# W681A.net
KiCad netlist of a schematic drawn in EAGLE
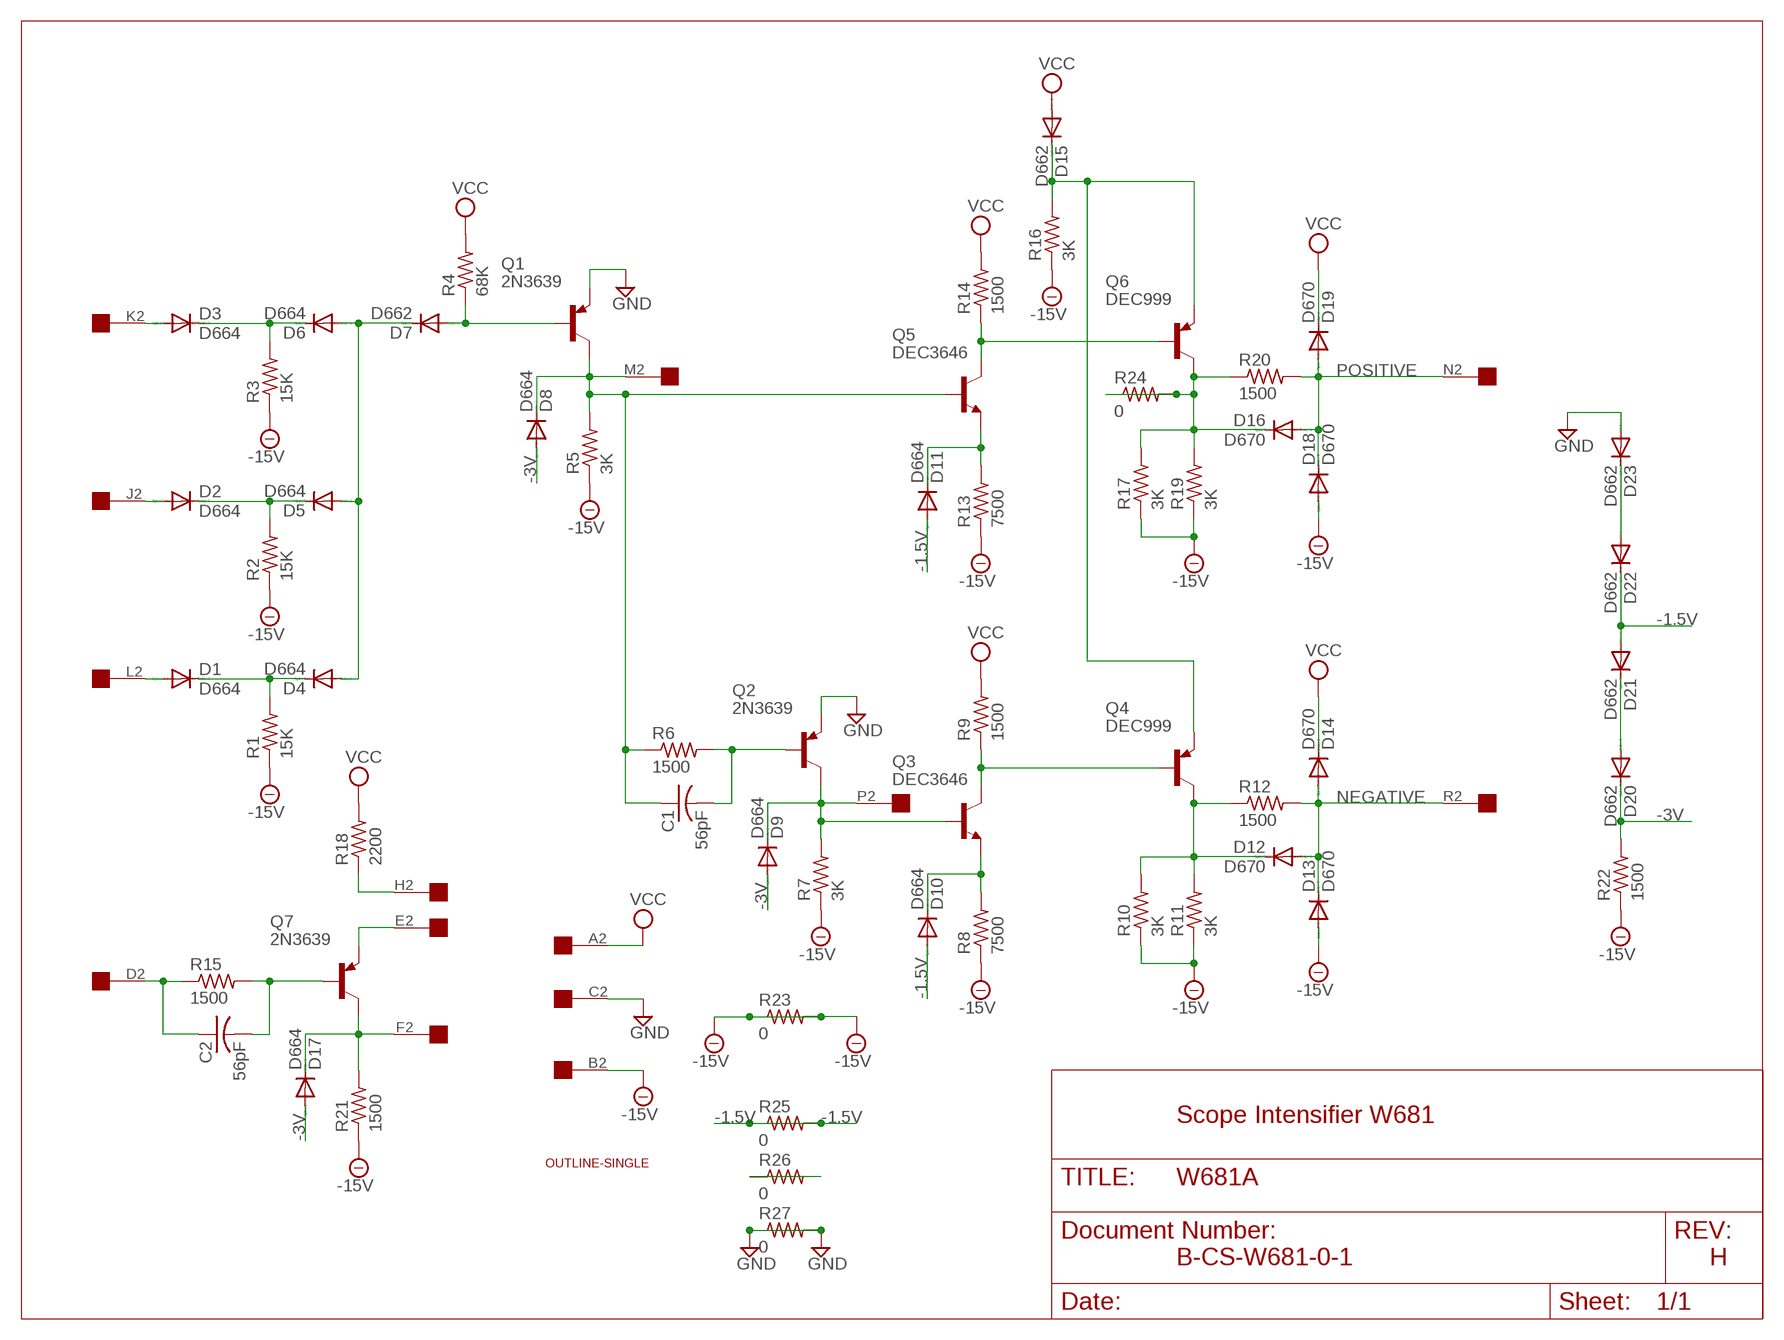
[diagram p0: schematic, sheet 1]

(export (version "E")
  (design (tool "Eeschema 10.0.6"))
  (components
    (comp (ref "C1")
      (value "56pF")
      (footprint "eagle-import:C063-025X075")
      (libsource (lib "eagle-import") (part "C-US"))
    )
    (comp (ref "C2")
      (value "56pF")
      (footprint "eagle-import:C063-025X075")
      (libsource (lib "eagle-import") (part "C-US"))
    )
    (comp (ref "D1")
      (value "D664")
      (footprint "eagle-import:DO35-10")
      (libsource (lib "eagle-import") (part "DIODE-DO35-10"))
    )
    (comp (ref "D2")
      (value "D664")
      (footprint "eagle-import:DO35-10")
      (libsource (lib "eagle-import") (part "DIODE-DO35-10"))
    )
    (comp (ref "D3")
      (value "D664")
      (footprint "eagle-import:DO35-10")
      (libsource (lib "eagle-import") (part "DIODE-DO35-10"))
    )
    (comp (ref "D4")
      (value "D664")
      (footprint "eagle-import:DO35-10")
      (libsource (lib "eagle-import") (part "DIODE-DO35-10"))
    )
    (comp (ref "D5")
      (value "D664")
      (footprint "eagle-import:DO35-10")
      (libsource (lib "eagle-import") (part "DIODE-DO35-10"))
    )
    (comp (ref "D6")
      (value "D664")
      (footprint "eagle-import:DO35-10")
      (libsource (lib "eagle-import") (part "DIODE-DO35-10"))
    )
    (comp (ref "D7")
      (value "D662")
      (footprint "eagle-import:DO35-10")
      (libsource (lib "eagle-import") (part "DIODE-DO35-10"))
    )
    (comp (ref "D8")
      (value "D664")
      (footprint "eagle-import:DO35-10")
      (libsource (lib "eagle-import") (part "DIODE-DO35-10"))
    )
    (comp (ref "D9")
      (value "D664")
      (footprint "eagle-import:DO35-10")
      (libsource (lib "eagle-import") (part "DIODE-DO35-10"))
    )
    (comp (ref "D10")
      (value "D664")
      (footprint "eagle-import:DO35-10")
      (libsource (lib "eagle-import") (part "DIODE-DO35-10"))
    )
    (comp (ref "D11")
      (value "D664")
      (footprint "eagle-import:DO35-10")
      (libsource (lib "eagle-import") (part "DIODE-DO35-10"))
    )
    (comp (ref "D12")
      (value "D670")
      (footprint "eagle-import:DO35-10")
      (libsource (lib "eagle-import") (part "DIODE-DO35-10"))
    )
    (comp (ref "D13")
      (value "D670")
      (footprint "eagle-import:DO35-10")
      (libsource (lib "eagle-import") (part "DIODE-DO35-10"))
    )
    (comp (ref "D14")
      (value "D670")
      (footprint "eagle-import:DO35-10")
      (libsource (lib "eagle-import") (part "DIODE-DO35-10"))
    )
    (comp (ref "D15")
      (value "D662")
      (footprint "eagle-import:DO35-10")
      (libsource (lib "eagle-import") (part "DIODE-DO35-10"))
    )
    (comp (ref "D16")
      (value "D670")
      (footprint "eagle-import:DO35-10")
      (libsource (lib "eagle-import") (part "DIODE-DO35-10"))
    )
    (comp (ref "D17")
      (value "D664")
      (footprint "eagle-import:DO35-10")
      (libsource (lib "eagle-import") (part "DIODE-DO35-10"))
    )
    (comp (ref "D18")
      (value "D670")
      (footprint "eagle-import:DO35-10")
      (libsource (lib "eagle-import") (part "DIODE-DO35-10"))
    )
    (comp (ref "D19")
      (value "D670")
      (footprint "eagle-import:DO35-10")
      (libsource (lib "eagle-import") (part "DIODE-DO35-10"))
    )
    (comp (ref "D20")
      (value "D662")
      (footprint "eagle-import:DO35-10")
      (libsource (lib "eagle-import") (part "DIODE-DO35-10"))
    )
    (comp (ref "D21")
      (value "D662")
      (footprint "eagle-import:DO35-10")
      (libsource (lib "eagle-import") (part "DIODE-DO35-10"))
    )
    (comp (ref "D22")
      (value "D662")
      (footprint "eagle-import:DO35-10")
      (libsource (lib "eagle-import") (part "DIODE-DO35-10"))
    )
    (comp (ref "D23")
      (value "D662")
      (footprint "eagle-import:DO35-10")
      (libsource (lib "eagle-import") (part "DIODE-DO35-10"))
    )
    (comp (ref "Q1")
      (value "2N3639")
      (footprint "eagle-import:TO5")
      (libsource (lib "eagle-import") (part "-PNP-TO5"))
    )
    (comp (ref "Q2")
      (value "2N3639")
      (footprint "eagle-import:TO5")
      (libsource (lib "eagle-import") (part "-PNP-TO5"))
    )
    (comp (ref "Q3")
      (value "DEC3646")
      (footprint "eagle-import:TO5")
      (libsource (lib "eagle-import") (part "-NPN-TO5"))
    )
    (comp (ref "Q4")
      (value "DEC999")
      (footprint "eagle-import:TO5")
      (libsource (lib "eagle-import") (part "-PNP-TO5"))
    )
    (comp (ref "Q5")
      (value "DEC3646")
      (footprint "eagle-import:TO5")
      (libsource (lib "eagle-import") (part "-NPN-TO5"))
    )
    (comp (ref "Q6")
      (value "DEC999")
      (footprint "eagle-import:TO5")
      (libsource (lib "eagle-import") (part "-PNP-TO5"))
    )
    (comp (ref "Q7")
      (value "2N3639")
      (footprint "eagle-import:TO5")
      (libsource (lib "eagle-import") (part "-PNP-TO5"))
    )
    (comp (ref "R1")
      (value "15K")
      (footprint "eagle-import:0207_10")
      (libsource (lib "eagle-import") (part "R-US_0207/10"))
    )
    (comp (ref "R2")
      (value "15K")
      (footprint "eagle-import:0207_10")
      (libsource (lib "eagle-import") (part "R-US_0207/10"))
    )
    (comp (ref "R3")
      (value "15K")
      (footprint "eagle-import:0207_10")
      (libsource (lib "eagle-import") (part "R-US_0207/10"))
    )
    (comp (ref "R4")
      (value "68K")
      (footprint "eagle-import:0207_10")
      (libsource (lib "eagle-import") (part "R-US_0207/10"))
    )
    (comp (ref "R5")
      (value "3K")
      (footprint "eagle-import:0207_10")
      (libsource (lib "eagle-import") (part "R-US_0207/10"))
    )
    (comp (ref "R6")
      (value "1500")
      (footprint "eagle-import:0207_10")
      (libsource (lib "eagle-import") (part "R-US_0207/10"))
    )
    (comp (ref "R7")
      (value "3K")
      (footprint "eagle-import:0207_10")
      (libsource (lib "eagle-import") (part "R-US_0207/10"))
    )
    (comp (ref "R8")
      (value "7500")
      (footprint "eagle-import:0207_10")
      (libsource (lib "eagle-import") (part "R-US_0207/10"))
    )
    (comp (ref "R9")
      (value "1500")
      (footprint "eagle-import:0207_10")
      (libsource (lib "eagle-import") (part "R-US_0207/10"))
    )
    (comp (ref "R10")
      (value "3K")
      (footprint "eagle-import:0207_10")
      (libsource (lib "eagle-import") (part "R-US_0207/10"))
    )
    (comp (ref "R11")
      (value "3K")
      (footprint "eagle-import:0207_10")
      (libsource (lib "eagle-import") (part "R-US_0207/10"))
    )
    (comp (ref "R12")
      (value "1500")
      (footprint "eagle-import:0207_10")
      (libsource (lib "eagle-import") (part "R-US_0207/10"))
    )
    (comp (ref "R13")
      (value "7500")
      (footprint "eagle-import:0207_10")
      (libsource (lib "eagle-import") (part "R-US_0207/10"))
    )
    (comp (ref "R14")
      (value "1500")
      (footprint "eagle-import:0207_10")
      (libsource (lib "eagle-import") (part "R-US_0207/10"))
    )
    (comp (ref "R15")
      (value "1500")
      (footprint "eagle-import:0207_10")
      (libsource (lib "eagle-import") (part "R-US_0207/10"))
    )
    (comp (ref "R16")
      (value "3K")
      (footprint "eagle-import:0207_10")
      (libsource (lib "eagle-import") (part "R-US_0207/10"))
    )
    (comp (ref "R17")
      (value "3K")
      (footprint "eagle-import:0207_10")
      (libsource (lib "eagle-import") (part "R-US_0207/10"))
    )
    (comp (ref "R18")
      (value "2200")
      (footprint "eagle-import:0207_10")
      (libsource (lib "eagle-import") (part "R-US_0207/10"))
    )
    (comp (ref "R19")
      (value "3K")
      (footprint "eagle-import:0207_10")
      (libsource (lib "eagle-import") (part "R-US_0207/10"))
    )
    (comp (ref "R20")
      (value "1500")
      (footprint "eagle-import:0207_10")
      (libsource (lib "eagle-import") (part "R-US_0207/10"))
    )
    (comp (ref "R21")
      (value "1500")
      (footprint "eagle-import:0207_10")
      (libsource (lib "eagle-import") (part "R-US_0207/10"))
    )
    (comp (ref "R22")
      (value "1500")
      (footprint "eagle-import:0207_10")
      (libsource (lib "eagle-import") (part "R-US_0207/10"))
    )
    (comp (ref "R23")
      (value "0")
      (footprint "eagle-import:0207_10")
      (libsource (lib "eagle-import") (part "R-US_0207/10"))
    )
    (comp (ref "R24")
      (value "0")
      (footprint "eagle-import:0207_10")
      (libsource (lib "eagle-import") (part "R-US_0207/10"))
    )
    (comp (ref "R25")
      (value "0")
      (footprint "eagle-import:0207_10")
      (libsource (lib "eagle-import") (part "R-US_0207/10"))
    )
    (comp (ref "R26")
      (value "0")
      (footprint "eagle-import:0207_10")
      (libsource (lib "eagle-import") (part "R-US_0207/10"))
    )
    (comp (ref "R27")
      (value "0")
      (footprint "eagle-import:0207_10")
      (libsource (lib "eagle-import") (part "R-US_0207/10"))
    )
    (comp (ref "U$1")
      (value "OUTLINE-SINGLE")
      (footprint "eagle-import:SINGLE")
      (libsource (lib "eagle-import") (part "OUTLINE-SINGLE"))
    )
    (comp (ref "U$2")
      (value "EDGE-1")
      (footprint "eagle-import:EDGE-CON1")
      (libsource (lib "eagle-import") (part "EDGE-1"))
    )
  )
  (nets
    (net (code "1") (name "-15V") (class "Default")
      (node (ref "D13") (pin "A") (pinfunction "A_A") (pintype "passive"))
      (node (ref "D18") (pin "A") (pinfunction "A_A") (pintype "passive"))
      (node (ref "R1") (pin "1") (pinfunction "1_1") (pintype "passive"))
      (node (ref "R10") (pin "1") (pinfunction "1_1") (pintype "passive"))
      (node (ref "R11") (pin "1") (pinfunction "1_1") (pintype "passive"))
      (node (ref "R13") (pin "1") (pinfunction "1_1") (pintype "passive"))
      (node (ref "R16") (pin "1") (pinfunction "1_1") (pintype "passive"))
      (node (ref "R17") (pin "1") (pinfunction "1_1") (pintype "passive"))
      (node (ref "R19") (pin "1") (pinfunction "1_1") (pintype "passive"))
      (node (ref "R2") (pin "1") (pinfunction "1_1") (pintype "passive"))
      (node (ref "R21") (pin "1") (pinfunction "1_1") (pintype "passive"))
      (node (ref "R22") (pin "1") (pinfunction "1_1") (pintype "passive"))
      (node (ref "R23") (pin "1") (pinfunction "1_1") (pintype "passive"))
      (node (ref "R23") (pin "2") (pinfunction "2_2") (pintype "passive"))
      (node (ref "R3") (pin "1") (pinfunction "1_1") (pintype "passive"))
      (node (ref "R5") (pin "1") (pinfunction "1_1") (pintype "passive"))
      (node (ref "R7") (pin "1") (pinfunction "1_1") (pintype "passive"))
      (node (ref "R8") (pin "1") (pinfunction "1_1") (pintype "passive"))
      (node (ref "U$2") (pin "B2") (pinfunction "1_B2") (pintype "bidirectional"))
    )
    (net (code "2") (name "/-1.5V") (class "Default")
      (node (ref "D10") (pin "A") (pinfunction "A_A") (pintype "passive"))
      (node (ref "D11") (pin "A") (pinfunction "A_A") (pintype "passive"))
      (node (ref "D21") (pin "A") (pinfunction "A_A") (pintype "passive"))
      (node (ref "D22") (pin "C") (pinfunction "C_C") (pintype "passive"))
      (node (ref "R25") (pin "1") (pinfunction "1_1") (pintype "passive"))
      (node (ref "R25") (pin "2") (pinfunction "2_2") (pintype "passive"))
    )
    (net (code "3") (name "/-3V") (class "Default")
      (node (ref "D17") (pin "A") (pinfunction "A_A") (pintype "passive"))
      (node (ref "D20") (pin "C") (pinfunction "C_C") (pintype "passive"))
      (node (ref "D8") (pin "A") (pinfunction "A_A") (pintype "passive"))
      (node (ref "D9") (pin "A") (pinfunction "A_A") (pintype "passive"))
      (node (ref "R22") (pin "2") (pinfunction "2_2") (pintype "passive"))
    )
    (net (code "4") (name "/NEGATIVE") (class "Default")
      (node (ref "D12") (pin "A") (pinfunction "A_A") (pintype "passive"))
      (node (ref "D13") (pin "C") (pinfunction "C_C") (pintype "passive"))
      (node (ref "D14") (pin "A") (pinfunction "A_A") (pintype "passive"))
      (node (ref "R12") (pin "2") (pinfunction "2_2") (pintype "passive"))
      (node (ref "U$2") (pin "R2") (pinfunction "1_R2") (pintype "bidirectional"))
    )
    (net (code "5") (name "/POSITIVE") (class "Default")
      (node (ref "D16") (pin "A") (pinfunction "A_A") (pintype "passive"))
      (node (ref "D18") (pin "C") (pinfunction "C_C") (pintype "passive"))
      (node (ref "D19") (pin "A") (pinfunction "A_A") (pintype "passive"))
      (node (ref "R20") (pin "2") (pinfunction "2_2") (pintype "passive"))
      (node (ref "U$2") (pin "N2") (pinfunction "1_N2") (pintype "bidirectional"))
    )
    (net (code "6") (name "GND") (class "Default")
      (node (ref "D23") (pin "A") (pinfunction "A_A") (pintype "passive"))
      (node (ref "Q1") (pin "1") (pinfunction "E_1") (pintype "passive"))
      (node (ref "Q2") (pin "1") (pinfunction "E_1") (pintype "passive"))
      (node (ref "R27") (pin "1") (pinfunction "1_1") (pintype "passive"))
      (node (ref "R27") (pin "2") (pinfunction "2_2") (pintype "passive"))
      (node (ref "U$2") (pin "C2") (pinfunction "1_C2") (pintype "bidirectional"))
    )
    (net (code "7") (name "Net-(D1-PadC)") (class "Default")
      (node (ref "D1") (pin "C") (pinfunction "C_C") (pintype "passive"))
      (node (ref "D4") (pin "C") (pinfunction "C_C") (pintype "passive"))
      (node (ref "R1") (pin "2") (pinfunction "2_2") (pintype "passive"))
    )
    (net (code "8") (name "Net-(D2-PadC)") (class "Default")
      (node (ref "D2") (pin "C") (pinfunction "C_C") (pintype "passive"))
      (node (ref "D5") (pin "C") (pinfunction "C_C") (pintype "passive"))
      (node (ref "R2") (pin "2") (pinfunction "2_2") (pintype "passive"))
    )
    (net (code "9") (name "Net-(D3-PadC)") (class "Default")
      (node (ref "D3") (pin "C") (pinfunction "C_C") (pintype "passive"))
      (node (ref "D6") (pin "C") (pinfunction "C_C") (pintype "passive"))
      (node (ref "R3") (pin "2") (pinfunction "2_2") (pintype "passive"))
    )
    (net (code "10") (name "Net-(D4-PadA)") (class "Default")
      (node (ref "D4") (pin "A") (pinfunction "A_A") (pintype "passive"))
      (node (ref "D5") (pin "A") (pinfunction "A_A") (pintype "passive"))
      (node (ref "D6") (pin "A") (pinfunction "A_A") (pintype "passive"))
      (node (ref "D7") (pin "C") (pinfunction "C_C") (pintype "passive"))
    )
    (net (code "11") (name "Net-(D20-PadA)") (class "Default")
      (node (ref "D20") (pin "A") (pinfunction "A_A") (pintype "passive"))
      (node (ref "D21") (pin "C") (pinfunction "C_C") (pintype "passive"))
    )
    (net (code "12") (name "Net-(D22-PadA)") (class "Default")
      (node (ref "D22") (pin "A") (pinfunction "A_A") (pintype "passive"))
      (node (ref "D23") (pin "C") (pinfunction "C_C") (pintype "passive"))
    )
    (net (code "13") (name "Net-(Q1-B)") (class "Default")
      (node (ref "D7") (pin "A") (pinfunction "A_A") (pintype "passive"))
      (node (ref "Q1") (pin "2") (pinfunction "B_2") (pintype "passive"))
      (node (ref "R4") (pin "1") (pinfunction "1_1") (pintype "passive"))
    )
    (net (code "14") (name "Net-(Q1-C)") (class "Default")
      (node (ref "C1") (pin "1") (pinfunction "1_1") (pintype "passive"))
      (node (ref "D8") (pin "C") (pinfunction "C_C") (pintype "passive"))
      (node (ref "Q1") (pin "3") (pinfunction "C_3") (pintype "passive"))
      (node (ref "Q5") (pin "2") (pinfunction "B_2") (pintype "passive"))
      (node (ref "R5") (pin "2") (pinfunction "2_2") (pintype "passive"))
      (node (ref "R6") (pin "1") (pinfunction "1_1") (pintype "passive"))
      (node (ref "U$2") (pin "M2") (pinfunction "1_M2") (pintype "bidirectional"))
    )
    (net (code "15") (name "Net-(Q2-B)") (class "Default")
      (node (ref "C1") (pin "2") (pinfunction "2_2") (pintype "passive"))
      (node (ref "Q2") (pin "2") (pinfunction "B_2") (pintype "passive"))
      (node (ref "R6") (pin "2") (pinfunction "2_2") (pintype "passive"))
    )
    (net (code "16") (name "Net-(Q2-C)") (class "Default")
      (node (ref "D9") (pin "C") (pinfunction "C_C") (pintype "passive"))
      (node (ref "Q2") (pin "3") (pinfunction "C_3") (pintype "passive"))
      (node (ref "Q3") (pin "2") (pinfunction "B_2") (pintype "passive"))
      (node (ref "R7") (pin "2") (pinfunction "2_2") (pintype "passive"))
      (node (ref "U$2") (pin "P2") (pinfunction "1_P2") (pintype "bidirectional"))
    )
    (net (code "17") (name "Net-(Q3-C)") (class "Default")
      (node (ref "Q3") (pin "3") (pinfunction "C_3") (pintype "passive"))
      (node (ref "Q4") (pin "2") (pinfunction "B_2") (pintype "passive"))
      (node (ref "R9") (pin "1") (pinfunction "1_1") (pintype "passive"))
    )
    (net (code "18") (name "Net-(Q3-E)") (class "Default")
      (node (ref "D10") (pin "C") (pinfunction "C_C") (pintype "passive"))
      (node (ref "Q3") (pin "1") (pinfunction "E_1") (pintype "passive"))
      (node (ref "R8") (pin "2") (pinfunction "2_2") (pintype "passive"))
    )
    (net (code "19") (name "Net-(Q4-C)") (class "Default")
      (node (ref "D12") (pin "C") (pinfunction "C_C") (pintype "passive"))
      (node (ref "Q4") (pin "3") (pinfunction "C_3") (pintype "passive"))
      (node (ref "R10") (pin "2") (pinfunction "2_2") (pintype "passive"))
      (node (ref "R11") (pin "2") (pinfunction "2_2") (pintype "passive"))
      (node (ref "R12") (pin "1") (pinfunction "1_1") (pintype "passive"))
    )
    (net (code "20") (name "Net-(Q4-E)") (class "Default")
      (node (ref "D15") (pin "C") (pinfunction "C_C") (pintype "passive"))
      (node (ref "Q4") (pin "1") (pinfunction "E_1") (pintype "passive"))
      (node (ref "Q6") (pin "1") (pinfunction "E_1") (pintype "passive"))
      (node (ref "R16") (pin "2") (pinfunction "2_2") (pintype "passive"))
    )
    (net (code "21") (name "Net-(Q5-C)") (class "Default")
      (node (ref "Q5") (pin "3") (pinfunction "C_3") (pintype "passive"))
      (node (ref "Q6") (pin "2") (pinfunction "B_2") (pintype "passive"))
      (node (ref "R14") (pin "1") (pinfunction "1_1") (pintype "passive"))
    )
    (net (code "22") (name "Net-(Q5-E)") (class "Default")
      (node (ref "D11") (pin "C") (pinfunction "C_C") (pintype "passive"))
      (node (ref "Q5") (pin "1") (pinfunction "E_1") (pintype "passive"))
      (node (ref "R13") (pin "2") (pinfunction "2_2") (pintype "passive"))
    )
    (net (code "23") (name "Net-(Q6-C)") (class "Default")
      (node (ref "D16") (pin "C") (pinfunction "C_C") (pintype "passive"))
      (node (ref "Q6") (pin "3") (pinfunction "C_3") (pintype "passive"))
      (node (ref "R17") (pin "2") (pinfunction "2_2") (pintype "passive"))
      (node (ref "R19") (pin "2") (pinfunction "2_2") (pintype "passive"))
      (node (ref "R20") (pin "1") (pinfunction "1_1") (pintype "passive"))
      (node (ref "R24") (pin "1") (pinfunction "1_1") (pintype "passive"))
      (node (ref "R24") (pin "2") (pinfunction "2_2") (pintype "passive"))
    )
    (net (code "24") (name "Net-(Q7-B)") (class "Default")
      (node (ref "C2") (pin "2") (pinfunction "2_2") (pintype "passive"))
      (node (ref "Q7") (pin "2") (pinfunction "B_2") (pintype "passive"))
      (node (ref "R15") (pin "2") (pinfunction "2_2") (pintype "passive"))
    )
    (net (code "25") (name "Net-(Q7-C)") (class "Default")
      (node (ref "D17") (pin "C") (pinfunction "C_C") (pintype "passive"))
      (node (ref "Q7") (pin "3") (pinfunction "C_3") (pintype "passive"))
      (node (ref "R21") (pin "2") (pinfunction "2_2") (pintype "passive"))
      (node (ref "U$2") (pin "F2") (pinfunction "1_F2") (pintype "bidirectional"))
    )
    (net (code "26") (name "Net-(Q7-E)") (class "Default")
      (node (ref "Q7") (pin "1") (pinfunction "E_1") (pintype "passive"))
      (node (ref "U$2") (pin "E2") (pinfunction "1_E2") (pintype "bidirectional"))
    )
    (net (code "27") (name "Net-(R26-Pad1)") (class "Default")
      (node (ref "R26") (pin "1") (pinfunction "1_1") (pintype "passive"))
      (node (ref "R26") (pin "2") (pinfunction "2_2") (pintype "passive"))
    )
    (net (code "28") (name "Net-(U$2D-1)") (class "Default")
      (node (ref "C2") (pin "1") (pinfunction "1_1") (pintype "passive"))
      (node (ref "R15") (pin "1") (pinfunction "1_1") (pintype "passive"))
      (node (ref "U$2") (pin "D2") (pinfunction "1_D2") (pintype "bidirectional"))
    )
    (net (code "29") (name "Net-(U$2G-1)") (class "Default")
      (node (ref "R18") (pin "1") (pinfunction "1_1") (pintype "passive"))
      (node (ref "U$2") (pin "H2") (pinfunction "1_H2") (pintype "bidirectional"))
    )
    (net (code "30") (name "Net-(U$2H-1)") (class "Default")
      (node (ref "D2") (pin "A") (pinfunction "A_A") (pintype "passive"))
      (node (ref "U$2") (pin "J2") (pinfunction "1_J2") (pintype "bidirectional"))
    )
    (net (code "31") (name "Net-(U$2I-1)") (class "Default")
      (node (ref "D3") (pin "A") (pinfunction "A_A") (pintype "passive"))
      (node (ref "U$2") (pin "K2") (pinfunction "1_K2") (pintype "bidirectional"))
    )
    (net (code "32") (name "Net-(U$2J-1)") (class "Default")
      (node (ref "D1") (pin "A") (pinfunction "A_A") (pintype "passive"))
      (node (ref "U$2") (pin "L2") (pinfunction "1_L2") (pintype "bidirectional"))
    )
    (net (code "33") (name "VCC") (class "Default")
      (node (ref "D14") (pin "C") (pinfunction "C_C") (pintype "passive"))
      (node (ref "D15") (pin "A") (pinfunction "A_A") (pintype "passive"))
      (node (ref "D19") (pin "C") (pinfunction "C_C") (pintype "passive"))
      (node (ref "R14") (pin "2") (pinfunction "2_2") (pintype "passive"))
      (node (ref "R18") (pin "2") (pinfunction "2_2") (pintype "passive"))
      (node (ref "R4") (pin "2") (pinfunction "2_2") (pintype "passive"))
      (node (ref "R9") (pin "2") (pinfunction "2_2") (pintype "passive"))
      (node (ref "U$2") (pin "A2") (pinfunction "1_A2") (pintype "bidirectional"))
    )
  )
)
